# EXTRUDER.net
KiCad netlist of a schematic drawn in EAGLE
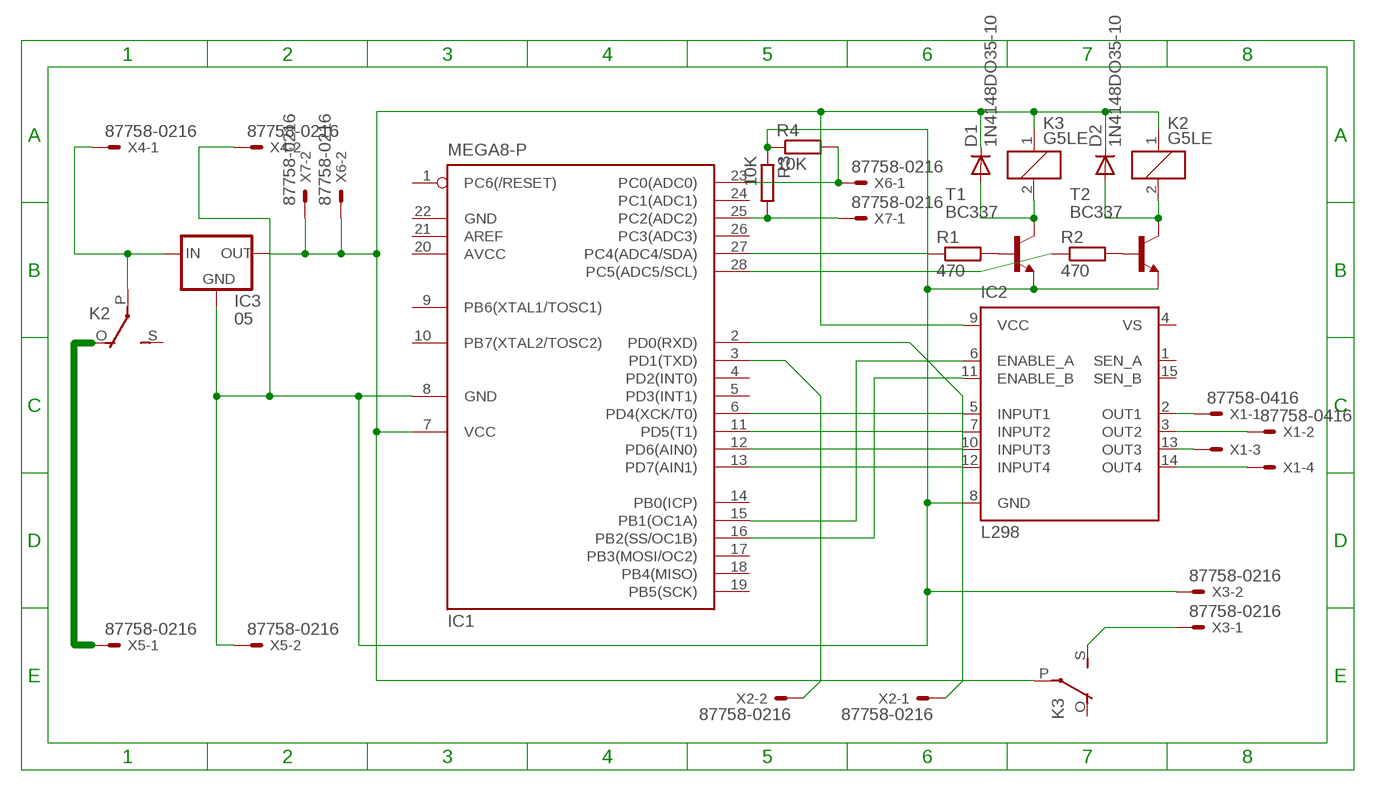
[diagram p0: schematic, sheet 1]

(export (version "E")
  (design (tool "Eeschema 10.0.6"))
  (components
    (comp (ref "D1")
      (value "1N4148DO35-10")
      (footprint "eagle-import:DO35-10")
      (libsource (lib "eagle-import") (part "1N4148DO35-10"))
    )
    (comp (ref "D2")
      (value "1N4148DO35-10")
      (footprint "eagle-import:DO35-10")
      (libsource (lib "eagle-import") (part "1N4148DO35-10"))
    )
    (comp (ref "IC1")
      (value "MEGA8-P")
      (footprint "eagle-import:DIL28-3")
      (libsource (lib "eagle-import") (part "MEGA8-P"))
    )
    (comp (ref "IC2")
      (value "L298")
      (footprint "eagle-import:MULTIWATT-15")
      (fields (field (name "MPN") "L298N"))
      (libsource (lib "eagle-import") (part "L298"))
    )
    (comp (ref "IC3")
      (value "05")
      (footprint "eagle-import:78XXL")
      (libsource (lib "eagle-import") (part "78XXL"))
    )
    (comp (ref "K2")
      (value "G5LE")
      (footprint "eagle-import:G5LE")
      (libsource (lib "eagle-import") (part "G5LE"))
    )
    (comp (ref "K3")
      (value "G5LE")
      (footprint "eagle-import:G5LE")
      (libsource (lib "eagle-import") (part "G5LE"))
    )
    (comp (ref "R1")
      (value "470")
      (footprint "eagle-import:0204_5")
      (libsource (lib "eagle-import") (part "R-EU_0204/5"))
    )
    (comp (ref "R2")
      (value "470")
      (footprint "eagle-import:0204_5")
      (libsource (lib "eagle-import") (part "R-EU_0204/5"))
    )
    (comp (ref "R3")
      (value "10K")
      (footprint "eagle-import:0204_5")
      (libsource (lib "eagle-import") (part "R-EU_0204/5"))
    )
    (comp (ref "R4")
      (value "10K")
      (footprint "eagle-import:0204_5")
      (libsource (lib "eagle-import") (part "R-EU_0204/5"))
    )
    (comp (ref "T1")
      (value "BC337")
      (footprint "eagle-import:TO92")
      (libsource (lib "eagle-import") (part "BC337"))
    )
    (comp (ref "T2")
      (value "BC337")
      (footprint "eagle-import:TO92")
      (libsource (lib "eagle-import") (part "BC337"))
    )
    (comp (ref "X1")
      (value "87758-0416")
      (footprint "eagle-import:87758-0416")
      (fields (field (name "MF") "FARNELL"))
      (libsource (lib "eagle-import") (part "87758-0416"))
    )
    (comp (ref "X2")
      (value "87758-0216")
      (footprint "eagle-import:87758-0216")
      (libsource (lib "eagle-import") (part "87758-0216"))
    )
    (comp (ref "X3")
      (value "87758-0216")
      (footprint "eagle-import:87758-0216")
      (libsource (lib "eagle-import") (part "87758-0216"))
    )
    (comp (ref "X4")
      (value "87758-0216")
      (footprint "eagle-import:87758-0216")
      (libsource (lib "eagle-import") (part "87758-0216"))
    )
    (comp (ref "X5")
      (value "87758-0216")
      (footprint "eagle-import:87758-0216")
      (libsource (lib "eagle-import") (part "87758-0216"))
    )
    (comp (ref "X6")
      (value "87758-0216")
      (footprint "eagle-import:87758-0216")
      (libsource (lib "eagle-import") (part "87758-0216"))
    )
    (comp (ref "X7")
      (value "87758-0216")
      (footprint "eagle-import:87758-0216")
      (libsource (lib "eagle-import") (part "87758-0216"))
    )
  )
  (nets
    (net (code "1") (name "/AVCC") (class "Default")
      (node (ref "IC1") (pin "20") (pinfunction "AVCC_20") (pintype "power_in"))
    )
    (net (code "2") (name "/GND") (class "Default")
      (node (ref "IC1") (pin "22") (pinfunction "GND_22") (pintype "power_in"))
    )
    (net (code "3") (name "/VS") (class "Default")
      (node (ref "IC2") (pin "4") (pinfunction "VS_4") (pintype "power_in"))
    )
    (net (code "4") (name "Net-(IC1-PB1(OC1A))") (class "Default")
      (node (ref "IC1") (pin "15") (pinfunction "PB1(OC1A)_15") (pintype "bidirectional"))
      (node (ref "IC2") (pin "6") (pinfunction "ENABLE_A_6") (pintype "input"))
    )
    (net (code "5") (name "Net-(IC1-PB2(SS{slash}OC1B))") (class "Default")
      (node (ref "IC1") (pin "16") (pinfunction "PB2(SS/OC1B)_16") (pintype "bidirectional"))
      (node (ref "IC2") (pin "11") (pinfunction "ENABLE_B_11") (pintype "input"))
    )
    (net (code "6") (name "Net-(IC1-PC0(ADC0))") (class "Default")
      (node (ref "IC1") (pin "23") (pinfunction "PC0(ADC0)_23") (pintype "bidirectional"))
      (node (ref "R4") (pin "2") (pinfunction "2_2") (pintype "passive"))
      (node (ref "X6") (pin "1") (pinfunction "S_1") (pintype "passive"))
    )
    (net (code "7") (name "Net-(IC1-PC2(ADC2))") (class "Default")
      (node (ref "IC1") (pin "25") (pinfunction "PC2(ADC2)_25") (pintype "bidirectional"))
      (node (ref "R3") (pin "2") (pinfunction "2_2") (pintype "passive"))
      (node (ref "X7") (pin "1") (pinfunction "S_1") (pintype "passive"))
    )
    (net (code "8") (name "Net-(IC1-PC4(ADC4{slash}SDA))") (class "Default")
      (node (ref "IC1") (pin "27") (pinfunction "PC4(ADC4/SDA)_27") (pintype "bidirectional"))
      (node (ref "R1") (pin "1") (pinfunction "1_1") (pintype "passive"))
    )
    (net (code "9") (name "Net-(IC1-PC5(ADC5{slash}SCL))") (class "Default")
      (node (ref "IC1") (pin "28") (pinfunction "PC5(ADC5/SCL)_28") (pintype "bidirectional"))
      (node (ref "R2") (pin "1") (pinfunction "1_1") (pintype "passive"))
    )
    (net (code "10") (name "Net-(IC1-PD0(RXD))") (class "Default")
      (node (ref "IC1") (pin "2") (pinfunction "PD0(RXD)_2") (pintype "bidirectional"))
      (node (ref "X2") (pin "1") (pinfunction "S_1") (pintype "passive"))
    )
    (net (code "11") (name "Net-(IC1-PD1(TXD))") (class "Default")
      (node (ref "IC1") (pin "3") (pinfunction "PD1(TXD)_3") (pintype "bidirectional"))
      (node (ref "X2") (pin "2") (pinfunction "S_2") (pintype "passive"))
    )
    (net (code "12") (name "Net-(IC1-PD4(XCK{slash}T0))") (class "Default")
      (node (ref "IC1") (pin "6") (pinfunction "PD4(XCK/T0)_6") (pintype "bidirectional"))
      (node (ref "IC2") (pin "5") (pinfunction "INPUT1_5") (pintype "input"))
    )
    (net (code "13") (name "Net-(IC1-PD5(T1))") (class "Default")
      (node (ref "IC1") (pin "11") (pinfunction "PD5(T1)_11") (pintype "bidirectional"))
      (node (ref "IC2") (pin "7") (pinfunction "INPUT2_7") (pintype "input"))
    )
    (net (code "14") (name "Net-(IC1-PD6(AIN0))") (class "Default")
      (node (ref "IC1") (pin "12") (pinfunction "PD6(AIN0)_12") (pintype "bidirectional"))
      (node (ref "IC2") (pin "10") (pinfunction "INPUT3_10") (pintype "input"))
    )
    (net (code "15") (name "Net-(IC1-PD7(AIN1))") (class "Default")
      (node (ref "IC1") (pin "13") (pinfunction "PD7(AIN1)_13") (pintype "bidirectional"))
      (node (ref "IC2") (pin "12") (pinfunction "INPUT4_12") (pintype "input"))
    )
    (net (code "16") (name "Net-(IC1-VCC)") (class "Default")
      (node (ref "D1") (pin "C") (pinfunction "C_C") (pintype "passive"))
      (node (ref "D2") (pin "C") (pinfunction "C_C") (pintype "passive"))
      (node (ref "IC1") (pin "7") (pinfunction "VCC_7") (pintype "power_in"))
      (node (ref "IC2") (pin "9") (pinfunction "VCC_9") (pintype "power_in"))
      (node (ref "IC3") (pin "OUT") (pinfunction "OUT_OUT") (pintype "passive"))
      (node (ref "K2") (pin "1") (pinfunction "1_1") (pintype "passive"))
      (node (ref "K3") (pin "1") (pinfunction "1_1") (pintype "passive"))
      (node (ref "K3") (pin "P") (pinfunction "P_P") (pintype "passive"))
      (node (ref "X6") (pin "2") (pinfunction "S_2") (pintype "passive"))
      (node (ref "X7") (pin "2") (pinfunction "S_2") (pintype "passive"))
    )
    (net (code "17") (name "Net-(IC2-GND)") (class "Default")
      (node (ref "IC1") (pin "8") (pinfunction "GND_8") (pintype "power_in"))
      (node (ref "IC2") (pin "8") (pinfunction "GND_8") (pintype "power_in"))
      (node (ref "IC3") (pin "GND") (pinfunction "GND_GND") (pintype "input"))
      (node (ref "R3") (pin "1") (pinfunction "1_1") (pintype "passive"))
      (node (ref "R4") (pin "1") (pinfunction "1_1") (pintype "passive"))
      (node (ref "T1") (pin "1") (pinfunction "E_1") (pintype "passive"))
      (node (ref "T2") (pin "1") (pinfunction "E_1") (pintype "passive"))
      (node (ref "X3") (pin "2") (pinfunction "S_2") (pintype "passive"))
      (node (ref "X4") (pin "2") (pinfunction "S_2") (pintype "passive"))
      (node (ref "X5") (pin "2") (pinfunction "S_2") (pintype "passive"))
    )
    (net (code "18") (name "Net-(IC2-OUT1)") (class "Default")
      (node (ref "IC2") (pin "2") (pinfunction "OUT1_2") (pintype "output"))
      (node (ref "X1") (pin "1") (pinfunction "S_1") (pintype "passive"))
    )
    (net (code "19") (name "Net-(IC2-OUT2)") (class "Default")
      (node (ref "IC2") (pin "3") (pinfunction "OUT2_3") (pintype "output"))
      (node (ref "X1") (pin "2") (pinfunction "S_2") (pintype "passive"))
    )
    (net (code "20") (name "Net-(IC2-OUT3)") (class "Default")
      (node (ref "IC2") (pin "13") (pinfunction "OUT3_13") (pintype "output"))
      (node (ref "X1") (pin "3") (pinfunction "S_3") (pintype "passive"))
    )
    (net (code "21") (name "Net-(IC2-OUT4)") (class "Default")
      (node (ref "IC2") (pin "14") (pinfunction "OUT4_14") (pintype "output"))
      (node (ref "X1") (pin "4") (pinfunction "S_4") (pintype "passive"))
    )
    (net (code "22") (name "Net-(T1-B)") (class "Default")
      (node (ref "R1") (pin "2") (pinfunction "2_2") (pintype "passive"))
      (node (ref "T1") (pin "2") (pinfunction "B_2") (pintype "passive"))
    )
    (net (code "23") (name "Net-(T1-C)") (class "Default")
      (node (ref "D1") (pin "A") (pinfunction "A_A") (pintype "passive"))
      (node (ref "K3") (pin "2") (pinfunction "2_2") (pintype "passive"))
      (node (ref "T1") (pin "3") (pinfunction "C_3") (pintype "passive"))
    )
    (net (code "24") (name "Net-(T2-B)") (class "Default")
      (node (ref "R2") (pin "2") (pinfunction "2_2") (pintype "passive"))
      (node (ref "T2") (pin "2") (pinfunction "B_2") (pintype "passive"))
    )
    (net (code "25") (name "Net-(T2-C)") (class "Default")
      (node (ref "D2") (pin "A") (pinfunction "A_A") (pintype "passive"))
      (node (ref "K2") (pin "2") (pinfunction "2_2") (pintype "passive"))
      (node (ref "T2") (pin "3") (pinfunction "C_3") (pintype "passive"))
    )
    (net (code "26") (name "Net-(X3A-S)") (class "Default")
      (node (ref "K3") (pin "S") (pinfunction "S_S") (pintype "passive"))
      (node (ref "X3") (pin "1") (pinfunction "S_1") (pintype "passive"))
    )
    (net (code "27") (name "Net-(X4A-S)") (class "Default")
      (node (ref "IC3") (pin "IN") (pinfunction "IN_IN") (pintype "input"))
      (node (ref "K2") (pin "P") (pinfunction "P_P") (pintype "passive"))
      (node (ref "X4") (pin "1") (pinfunction "S_1") (pintype "passive"))
    )
    (net (code "28") (name "Net-(X5A-S)") (class "Default")
      (node (ref "K2") (pin "O") (pinfunction "O_O") (pintype "passive"))
      (node (ref "X5") (pin "1") (pinfunction "S_1") (pintype "passive"))
    )
    (net (code "29") (name "unconnected-(IC1-AREF-Pad21)") (class "Default")
      (node (ref "IC1") (pin "21") (pinfunction "AREF_21") (pintype "passive"))
    )
    (net (code "30") (name "unconnected-(IC1-PB0(ICP)-Pad14)") (class "Default")
      (node (ref "IC1") (pin "14") (pinfunction "PB0(ICP)_14") (pintype "bidirectional"))
    )
    (net (code "31") (name "unconnected-(IC1-PB3(MOSI{slash}OC2)-Pad17)") (class "Default")
      (node (ref "IC1") (pin "17") (pinfunction "PB3(MOSI/OC2)_17") (pintype "bidirectional"))
    )
    (net (code "32") (name "unconnected-(IC1-PB4(MISO)-Pad18)") (class "Default")
      (node (ref "IC1") (pin "18") (pinfunction "PB4(MISO)_18") (pintype "bidirectional"))
    )
    (net (code "33") (name "unconnected-(IC1-PB5(SCK)-Pad19)") (class "Default")
      (node (ref "IC1") (pin "19") (pinfunction "PB5(SCK)_19") (pintype "bidirectional"))
    )
    (net (code "34") (name "unconnected-(IC1-PB6(XTAL1{slash}TOSC1)-Pad9)") (class "Default")
      (node (ref "IC1") (pin "9") (pinfunction "PB6(XTAL1/TOSC1)_9") (pintype "bidirectional"))
    )
    (net (code "35") (name "unconnected-(IC1-PB7(XTAL2{slash}TOSC2)-Pad10)") (class "Default")
      (node (ref "IC1") (pin "10") (pinfunction "PB7(XTAL2/TOSC2)_10") (pintype "bidirectional"))
    )
    (net (code "36") (name "unconnected-(IC1-PC1(ADC1)-Pad24)") (class "Default")
      (node (ref "IC1") (pin "24") (pinfunction "PC1(ADC1)_24") (pintype "bidirectional"))
    )
    (net (code "37") (name "unconnected-(IC1-PC3(ADC3)-Pad26)") (class "Default")
      (node (ref "IC1") (pin "26") (pinfunction "PC3(ADC3)_26") (pintype "bidirectional"))
    )
    (net (code "38") (name "unconnected-(IC1-PC6({slash}RESET)-Pad1)") (class "Default")
      (node (ref "IC1") (pin "1") (pinfunction "PC6(/RESET)_1") (pintype "bidirectional"))
    )
    (net (code "39") (name "unconnected-(IC1-PD2(INT0)-Pad4)") (class "Default")
      (node (ref "IC1") (pin "4") (pinfunction "PD2(INT0)_4") (pintype "bidirectional"))
    )
    (net (code "40") (name "unconnected-(IC1-PD3(INT1)-Pad5)") (class "Default")
      (node (ref "IC1") (pin "5") (pinfunction "PD3(INT1)_5") (pintype "bidirectional"))
    )
    (net (code "41") (name "unconnected-(IC2-SEN_A-Pad1)") (class "Default")
      (node (ref "IC2") (pin "1") (pinfunction "SEN_A_1") (pintype "input"))
    )
    (net (code "42") (name "unconnected-(IC2-SEN_B-Pad15)") (class "Default")
      (node (ref "IC2") (pin "15") (pinfunction "SEN_B_15") (pintype "input"))
    )
    (net (code "43") (name "unconnected-(K2-PadS)") (class "Default")
      (node (ref "K2") (pin "S") (pinfunction "S_S") (pintype "passive"))
    )
    (net (code "44") (name "unconnected-(K3-PadO)") (class "Default")
      (node (ref "K3") (pin "O") (pinfunction "O_O") (pintype "passive"))
    )
  )
)
